# Digital_-_STM32.net
KiCad netlist of a schematic drawn in Altium Designer
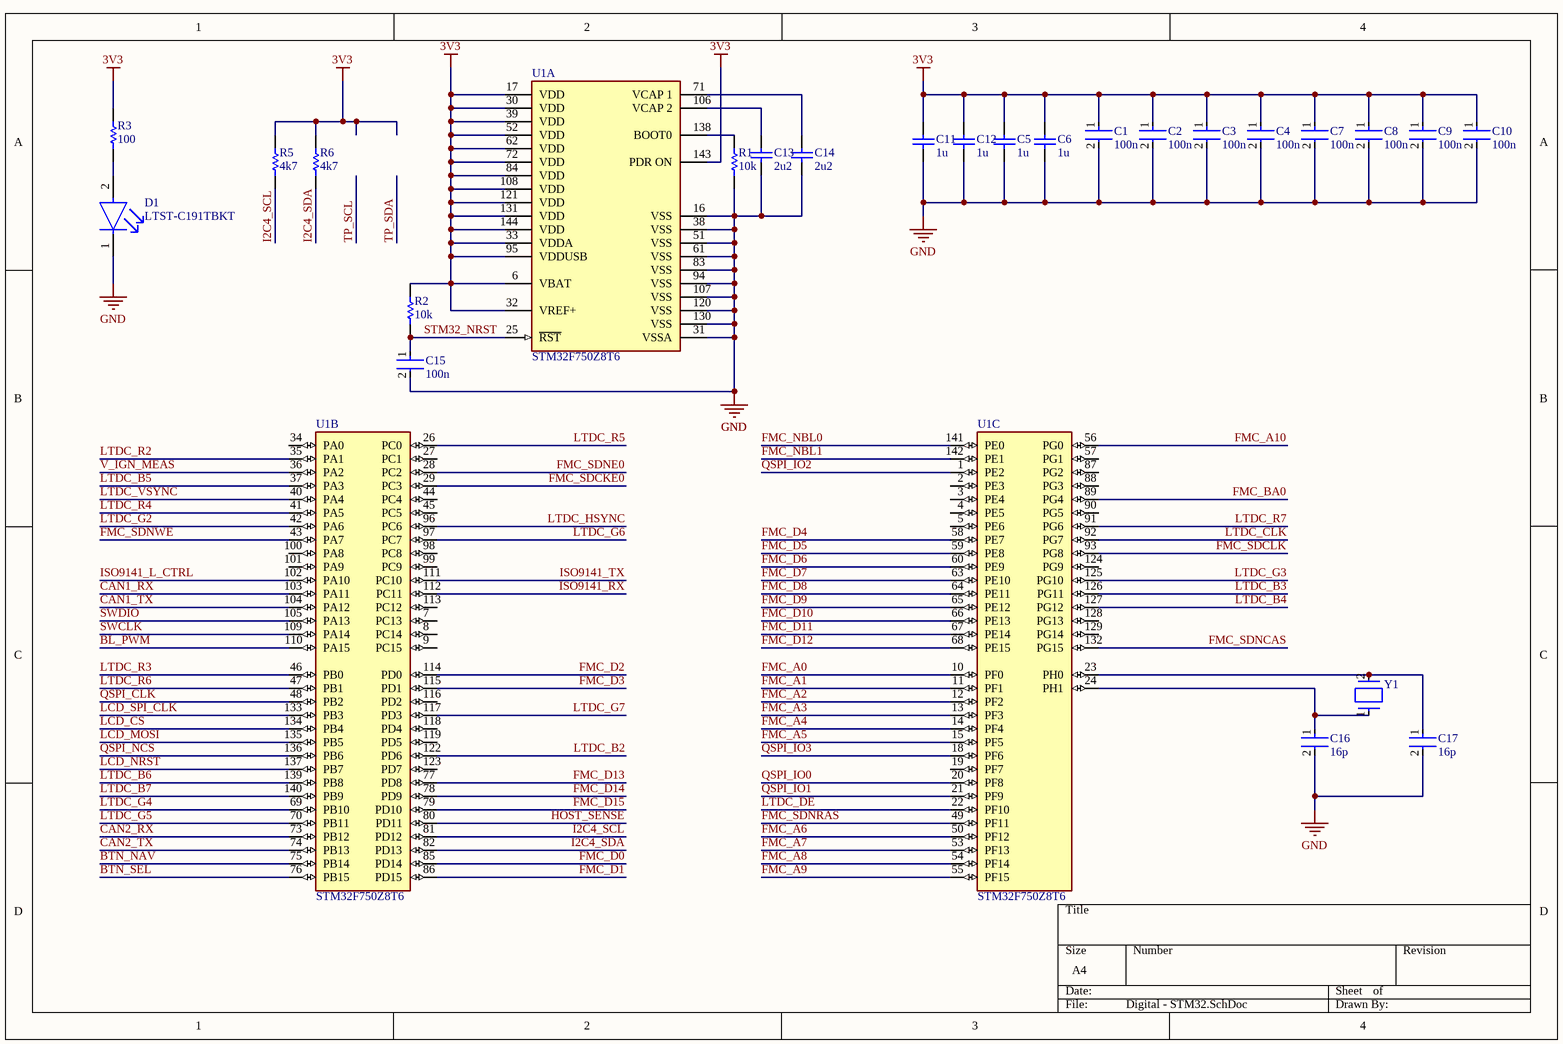
[diagram p0: Digital - STM32.SchDoc]

(export (version "E")
  (design (tool "Eeschema 10.0.6"))
  (components
    (comp (ref "C1")
      (value "100n")
      (footprint "FP-GRM188-0_1-e0_2_0_55-IPC_A")
      (description "Chip Multilayer Ceramic Capacitors for General Purpose, 0603, 10uF, X5R, 15%, 20%, 6.3V")
      (fields (field (name "VOLTAGE") "6.3V") (field (name "TOLERANCE") "20%"))
      (libsource (lib "Altium Content Vault") (part "02cd4be3c70576c341d710602a673aa"))
    )
    (comp (ref "C2")
      (value "100n")
      (footprint "FP-GRM188-0_1-e0_2_0_55-IPC_A")
      (description "Chip Multilayer Ceramic Capacitors for General Purpose, 0603, 10uF, X5R, 15%, 20%, 6.3V")
      (fields (field (name "VOLTAGE") "6.3V") (field (name "TOLERANCE") "20%"))
      (libsource (lib "Altium Content Vault") (part "02cd4be3c70576c341d710602a673aa"))
    )
    (comp (ref "C3")
      (value "100n")
      (footprint "FP-GRM188-0_1-e0_2_0_55-IPC_A")
      (description "Chip Multilayer Ceramic Capacitors for General Purpose, 0603, 10uF, X5R, 15%, 20%, 6.3V")
      (fields (field (name "VOLTAGE") "6.3V") (field (name "TOLERANCE") "20%"))
      (libsource (lib "Altium Content Vault") (part "02cd4be3c70576c341d710602a673aa"))
    )
    (comp (ref "C4")
      (value "100n")
      (footprint "FP-GRM188-0_1-e0_2_0_55-IPC_A")
      (description "Chip Multilayer Ceramic Capacitors for General Purpose, 0603, 10uF, X5R, 15%, 20%, 6.3V")
      (fields (field (name "VOLTAGE") "6.3V") (field (name "TOLERANCE") "20%"))
      (libsource (lib "Altium Content Vault") (part "02cd4be3c70576c341d710602a673aa"))
    )
    (comp (ref "C5")
      (value "1u")
      (footprint "CAPC2013X135X45LL10T25")
      (description "Chip Capacitor, 4.7 uF, +/- 10%, 16 V, -55 to 85 degC, 0805 (2012 Metric), RoHS, Tape and Reel")
      (fields (field (name "TOLERANCE") "10%") (field (name "PARTNUMBER") "GRM21BR61C475KA88L"))
      (libsource (lib "Altium Content Vault") (part "CAP-NP-2"))
    )
    (comp (ref "C6")
      (value "1u")
      (footprint "CAPC2013X135X45LL10T25")
      (description "Chip Capacitor, 4.7 uF, +/- 10%, 16 V, -55 to 85 degC, 0805 (2012 Metric), RoHS, Tape and Reel")
      (fields (field (name "TOLERANCE") "10%") (field (name "PARTNUMBER") "GRM21BR61C475KA88L"))
      (libsource (lib "Altium Content Vault") (part "CAP-NP-2"))
    )
    (comp (ref "C7")
      (value "100n")
      (footprint "FP-GRM188-0_1-e0_2_0_55-IPC_A")
      (description "Chip Multilayer Ceramic Capacitors for General Purpose, 0603, 10uF, X5R, 15%, 20%, 6.3V")
      (fields (field (name "VOLTAGE") "6.3V") (field (name "TOLERANCE") "20%"))
      (libsource (lib "Altium Content Vault") (part "02cd4be3c70576c341d710602a673aa"))
    )
    (comp (ref "C8")
      (value "100n")
      (footprint "FP-GRM188-0_1-e0_2_0_55-IPC_A")
      (description "Chip Multilayer Ceramic Capacitors for General Purpose, 0603, 10uF, X5R, 15%, 20%, 6.3V")
      (fields (field (name "VOLTAGE") "6.3V") (field (name "TOLERANCE") "20%"))
      (libsource (lib "Altium Content Vault") (part "02cd4be3c70576c341d710602a673aa"))
    )
    (comp (ref "C9")
      (value "100n")
      (footprint "FP-GRM188-0_1-e0_2_0_55-IPC_A")
      (description "Chip Multilayer Ceramic Capacitors for General Purpose, 0603, 10uF, X5R, 15%, 20%, 6.3V")
      (fields (field (name "VOLTAGE") "6.3V") (field (name "TOLERANCE") "20%"))
      (libsource (lib "Altium Content Vault") (part "02cd4be3c70576c341d710602a673aa"))
    )
    (comp (ref "C10")
      (value "100n")
      (footprint "FP-GRM188-0_1-e0_2_0_55-IPC_A")
      (description "Chip Multilayer Ceramic Capacitors for General Purpose, 0603, 10uF, X5R, 15%, 20%, 6.3V")
      (fields (field (name "VOLTAGE") "6.3V") (field (name "TOLERANCE") "20%"))
      (libsource (lib "Altium Content Vault") (part "02cd4be3c70576c341d710602a673aa"))
    )
    (comp (ref "C11")
      (value "1u")
      (footprint "CAPC2013X135X45LL10T25")
      (description "Chip Capacitor, 4.7 uF, +/- 10%, 16 V, -55 to 85 degC, 0805 (2012 Metric), RoHS, Tape and Reel")
      (fields (field (name "TOLERANCE") "10%") (field (name "PARTNUMBER") "GRM21BR61C475KA88L"))
      (libsource (lib "Altium Content Vault") (part "CAP-NP-2"))
    )
    (comp (ref "C12")
      (value "1u")
      (footprint "CAPC2013X135X45LL10T25")
      (description "Chip Capacitor, 4.7 uF, +/- 10%, 16 V, -55 to 85 degC, 0805 (2012 Metric), RoHS, Tape and Reel")
      (fields (field (name "TOLERANCE") "10%") (field (name "PARTNUMBER") "GRM21BR61C475KA88L"))
      (libsource (lib "Altium Content Vault") (part "CAP-NP-2"))
    )
    (comp (ref "C13")
      (value "2u2")
      (footprint "CAPC2013X135X45LL10T25")
      (description "Chip Capacitor, 4.7 uF, +/- 10%, 16 V, -55 to 85 degC, 0805 (2012 Metric), RoHS, Tape and Reel")
      (fields (field (name "TOLERANCE") "10%") (field (name "PARTNUMBER") "GRM21BR61C475KA88L"))
      (libsource (lib "Altium Content Vault") (part "CAP-NP-2"))
    )
    (comp (ref "C14")
      (value "2u2")
      (footprint "CAPC2013X135X45LL10T25")
      (description "Chip Capacitor, 4.7 uF, +/- 10%, 16 V, -55 to 85 degC, 0805 (2012 Metric), RoHS, Tape and Reel")
      (fields (field (name "TOLERANCE") "10%") (field (name "PARTNUMBER") "GRM21BR61C475KA88L"))
      (libsource (lib "Altium Content Vault") (part "CAP-NP-2"))
    )
    (comp (ref "C15")
      (value "100n")
      (footprint "FP-GRM188-0_1-e0_2_0_55-IPC_A")
      (description "Chip Multilayer Ceramic Capacitors for General Purpose, 0603, 10uF, X5R, 15%, 20%, 6.3V")
      (fields (field (name "VOLTAGE") "6.3V") (field (name "TOLERANCE") "20%"))
      (libsource (lib "Altium Content Vault") (part "02cd4be3c70576c341d710602a673aa"))
    )
    (comp (ref "C16")
      (value "16p")
      (footprint "FP-GRM188-0_1-e0_2_0_55-IPC_A")
      (description "Chip Multilayer Ceramic Capacitors for General Purpose, 0603, 10uF, X5R, 15%, 20%, 6.3V")
      (fields (field (name "VOLTAGE") "6.3V") (field (name "TOLERANCE") "20%"))
      (libsource (lib "Altium Content Vault") (part "02cd4be3c70576c341d710602a673aa"))
    )
    (comp (ref "C17")
      (value "16p")
      (footprint "FP-GRM188-0_1-e0_2_0_55-IPC_A")
      (description "Chip Multilayer Ceramic Capacitors for General Purpose, 0603, 10uF, X5R, 15%, 20%, 6.3V")
      (fields (field (name "VOLTAGE") "6.3V") (field (name "TOLERANCE") "20%"))
      (libsource (lib "Altium Content Vault") (part "02cd4be3c70576c341d710602a673aa"))
    )
    (comp (ref "D1")
      (value "LTST-C191TBKT")
      (footprint "FP-LTST-C191TBKT-MFG")
      (description "LED BLUE CLEAR CHIP SMD")
      (libsource (lib "Altium Content Vault") (part "8706943c75ba83719d021d2fdc84c58"))
    )
    (comp (ref "R1")
      (value "10k")
      (footprint "RESC1608X55X30ML15T15")
      (fields (field (name "PART NUMBER") "ERJ-3EKF1003V") (field (name "MANUFACTURER") "Panasonic"))
      (libsource (lib "Altium Content Vault") (part "RES"))
    )
    (comp (ref "R2")
      (value "10k")
      (footprint "RESC1608X55X30ML15T15")
      (fields (field (name "PART NUMBER") "ERJ-3EKF1003V") (field (name "MANUFACTURER") "Panasonic"))
      (libsource (lib "Altium Content Vault") (part "RES"))
    )
    (comp (ref "R3")
      (value "100")
      (footprint "RESC1608X55X30ML15T15")
      (fields (field (name "PART NUMBER") "ERJ-3EKF1003V") (field (name "MANUFACTURER") "Panasonic"))
      (libsource (lib "Altium Content Vault") (part "RES"))
    )
    (comp (ref "R5")
      (value "4k7")
      (footprint "RESC1608X55X30ML15T15")
      (fields (field (name "PART NUMBER") "ERJ-3EKF1003V") (field (name "MANUFACTURER") "Panasonic"))
      (libsource (lib "Altium Content Vault") (part "RES"))
    )
    (comp (ref "R6")
      (value "4k7")
      (footprint "RESC1608X55X30ML15T15")
      (fields (field (name "PART NUMBER") "ERJ-3EKF1003V") (field (name "MANUFACTURER") "Panasonic"))
      (libsource (lib "Altium Content Vault") (part "RES"))
    )
    (comp (ref "U1")
      (value "STM32F750Z8T6")
      (footprint "FP-LQFP144-1A-MFG")
      (description "IC MCU 32BIT 64KB FLASH 144LQFP")
      (fields
        (field (name "MANUFACTURER") "STMicroelectronics")
        (field (name "OCTOPART") "https://octopart.com/stm32f750z8t6-stmicroelectronics-94048545")
      )
      (libsource (lib "Altium Content Vault") (part "1b3660c51b2871d5e5de1e944f1bdf6"))
    )
    (comp (ref "Y1")
      (value "ABM7-16.000MHZ-D2Y-T")
      (footprint "FP-ABM7-MFG")
      (description "Crystal 16MHz ±20ppm 18pF SMD-2 6mm x 3.5mm")
      (fields (field (name "TOLERANCE") "20ppm"))
      (libsource (lib "Altium Content Vault") (part "c23a69dc6c9e2f18f2079038eb95dd1"))
    )
  )
  (nets
    (net (code "1") (name "/BL_PWM") (class "Default")
      (node (ref "U1") (pin "110") (pinfunction "PA15_110") (pintype "bidirectional"))
    )
    (net (code "2") (name "/BTN_NAV") (class "Default")
      (node (ref "U1") (pin "75") (pinfunction "PB14_75") (pintype "bidirectional"))
    )
    (net (code "3") (name "/BTN_SEL") (class "Default")
      (node (ref "U1") (pin "76") (pinfunction "PB15_76") (pintype "bidirectional"))
    )
    (net (code "4") (name "/CAN1_RX") (class "Default")
      (node (ref "U1") (pin "103") (pinfunction "PA11_103") (pintype "bidirectional"))
    )
    (net (code "5") (name "/CAN1_TX") (class "Default")
      (node (ref "U1") (pin "104") (pinfunction "PA12_104") (pintype "bidirectional"))
    )
    (net (code "6") (name "/CAN2_RX") (class "Default")
      (node (ref "U1") (pin "73") (pinfunction "PB12_73") (pintype "bidirectional"))
    )
    (net (code "7") (name "/CAN2_TX") (class "Default")
      (node (ref "U1") (pin "74") (pinfunction "PB13_74") (pintype "bidirectional"))
    )
    (net (code "8") (name "/FMC_A0") (class "Default")
      (node (ref "U1") (pin "10") (pinfunction "PF0_10") (pintype "bidirectional"))
    )
    (net (code "9") (name "/FMC_A1") (class "Default")
      (node (ref "U1") (pin "11") (pinfunction "PF1_11") (pintype "bidirectional"))
    )
    (net (code "10") (name "/FMC_A2") (class "Default")
      (node (ref "U1") (pin "12") (pinfunction "PF2_12") (pintype "bidirectional"))
    )
    (net (code "11") (name "/FMC_A3") (class "Default")
      (node (ref "U1") (pin "13") (pinfunction "PF3_13") (pintype "bidirectional"))
    )
    (net (code "12") (name "/FMC_A4") (class "Default")
      (node (ref "U1") (pin "14") (pinfunction "PF4_14") (pintype "bidirectional"))
    )
    (net (code "13") (name "/FMC_A5") (class "Default")
      (node (ref "U1") (pin "15") (pinfunction "PF5_15") (pintype "bidirectional"))
    )
    (net (code "14") (name "/FMC_A6") (class "Default")
      (node (ref "U1") (pin "50") (pinfunction "PF12_50") (pintype "bidirectional"))
    )
    (net (code "15") (name "/FMC_A7") (class "Default")
      (node (ref "U1") (pin "53") (pinfunction "PF13_53") (pintype "bidirectional"))
    )
    (net (code "16") (name "/FMC_A8") (class "Default")
      (node (ref "U1") (pin "54") (pinfunction "PF14_54") (pintype "bidirectional"))
    )
    (net (code "17") (name "/FMC_A9") (class "Default")
      (node (ref "U1") (pin "55") (pinfunction "PF15_55") (pintype "bidirectional"))
    )
    (net (code "18") (name "/FMC_A10") (class "Default")
      (node (ref "U1") (pin "56") (pinfunction "PG0_56") (pintype "bidirectional"))
    )
    (net (code "19") (name "/FMC_BA0") (class "Default")
      (node (ref "U1") (pin "89") (pinfunction "PG4_89") (pintype "bidirectional"))
    )
    (net (code "20") (name "/FMC_D0") (class "Default")
      (node (ref "U1") (pin "85") (pinfunction "PD14_85") (pintype "bidirectional"))
    )
    (net (code "21") (name "/FMC_D1") (class "Default")
      (node (ref "U1") (pin "86") (pinfunction "PD15_86") (pintype "bidirectional"))
    )
    (net (code "22") (name "/FMC_D2") (class "Default")
      (node (ref "U1") (pin "114") (pinfunction "PD0_114") (pintype "bidirectional"))
    )
    (net (code "23") (name "/FMC_D3") (class "Default")
      (node (ref "U1") (pin "115") (pinfunction "PD1_115") (pintype "bidirectional"))
    )
    (net (code "24") (name "/FMC_D4") (class "Default")
      (node (ref "U1") (pin "58") (pinfunction "PE7_58") (pintype "bidirectional"))
    )
    (net (code "25") (name "/FMC_D5") (class "Default")
      (node (ref "U1") (pin "59") (pinfunction "PE8_59") (pintype "bidirectional"))
    )
    (net (code "26") (name "/FMC_D6") (class "Default")
      (node (ref "U1") (pin "60") (pinfunction "PE9_60") (pintype "bidirectional"))
    )
    (net (code "27") (name "/FMC_D7") (class "Default")
      (node (ref "U1") (pin "63") (pinfunction "PE10_63") (pintype "bidirectional"))
    )
    (net (code "28") (name "/FMC_D8") (class "Default")
      (node (ref "U1") (pin "64") (pinfunction "PE11_64") (pintype "bidirectional"))
    )
    (net (code "29") (name "/FMC_D9") (class "Default")
      (node (ref "U1") (pin "65") (pinfunction "PE12_65") (pintype "bidirectional"))
    )
    (net (code "30") (name "/FMC_D10") (class "Default")
      (node (ref "U1") (pin "66") (pinfunction "PE13_66") (pintype "bidirectional"))
    )
    (net (code "31") (name "/FMC_D11") (class "Default")
      (node (ref "U1") (pin "67") (pinfunction "PE14_67") (pintype "bidirectional"))
    )
    (net (code "32") (name "/FMC_D12") (class "Default")
      (node (ref "U1") (pin "68") (pinfunction "PE15_68") (pintype "bidirectional"))
    )
    (net (code "33") (name "/FMC_D13") (class "Default")
      (node (ref "U1") (pin "77") (pinfunction "PD8_77") (pintype "bidirectional"))
    )
    (net (code "34") (name "/FMC_D14") (class "Default")
      (node (ref "U1") (pin "78") (pinfunction "PD9_78") (pintype "bidirectional"))
    )
    (net (code "35") (name "/FMC_D15") (class "Default")
      (node (ref "U1") (pin "79") (pinfunction "PD10_79") (pintype "bidirectional"))
    )
    (net (code "36") (name "/FMC_NBL0") (class "Default")
      (node (ref "U1") (pin "141") (pinfunction "PE0_141") (pintype "bidirectional"))
    )
    (net (code "37") (name "/FMC_NBL1") (class "Default")
      (node (ref "U1") (pin "142") (pinfunction "PE1_142") (pintype "bidirectional"))
    )
    (net (code "38") (name "/FMC_SDCKE0") (class "Default")
      (node (ref "U1") (pin "29") (pinfunction "PC3_29") (pintype "bidirectional"))
    )
    (net (code "39") (name "/FMC_SDCLK") (class "Default")
      (node (ref "U1") (pin "93") (pinfunction "PG8_93") (pintype "bidirectional"))
    )
    (net (code "40") (name "/FMC_SDNCAS") (class "Default")
      (node (ref "U1") (pin "132") (pinfunction "PG15_132") (pintype "bidirectional"))
    )
    (net (code "41") (name "/FMC_SDNE0") (class "Default")
      (node (ref "U1") (pin "28") (pinfunction "PC2_28") (pintype "bidirectional"))
    )
    (net (code "42") (name "/FMC_SDNRAS") (class "Default")
      (node (ref "U1") (pin "49") (pinfunction "PF11_49") (pintype "bidirectional"))
    )
    (net (code "43") (name "/FMC_SDNWE") (class "Default")
      (node (ref "U1") (pin "43") (pinfunction "PA7_43") (pintype "bidirectional"))
    )
    (net (code "44") (name "/HOST_SENSE") (class "Default")
      (node (ref "U1") (pin "80") (pinfunction "PD11_80") (pintype "bidirectional"))
    )
    (net (code "45") (name "/I2C4_SCL") (class "Default")
      (node (ref "R5") (pin "1") (pinfunction "1_1") (pintype "passive"))
      (node (ref "U1") (pin "81") (pinfunction "PD12_81") (pintype "bidirectional"))
    )
    (net (code "46") (name "/I2C4_SDA") (class "Default")
      (node (ref "R6") (pin "1") (pinfunction "1_1") (pintype "passive"))
      (node (ref "U1") (pin "82") (pinfunction "PD13_82") (pintype "bidirectional"))
    )
    (net (code "47") (name "/ISO9141_L_CTRL") (class "Default")
      (node (ref "U1") (pin "102") (pinfunction "PA10_102") (pintype "bidirectional"))
    )
    (net (code "48") (name "/ISO9141_RX") (class "Default")
      (node (ref "U1") (pin "112") (pinfunction "PC11_112") (pintype "bidirectional"))
    )
    (net (code "49") (name "/ISO9141_TX") (class "Default")
      (node (ref "U1") (pin "111") (pinfunction "PC10_111") (pintype "bidirectional"))
    )
    (net (code "50") (name "/LCD_CS") (class "Default")
      (node (ref "U1") (pin "134") (pinfunction "PB4_134") (pintype "bidirectional"))
    )
    (net (code "51") (name "/LCD_MOSI") (class "Default")
      (node (ref "U1") (pin "135") (pinfunction "PB5_135") (pintype "bidirectional"))
    )
    (net (code "52") (name "/LCD_NRST") (class "Default")
      (node (ref "U1") (pin "137") (pinfunction "PB7_137") (pintype "bidirectional"))
    )
    (net (code "53") (name "/LCD_SPI_CLK") (class "Default")
      (node (ref "U1") (pin "133") (pinfunction "PB3_133") (pintype "bidirectional"))
    )
    (net (code "54") (name "/LTDC_B2") (class "Default")
      (node (ref "U1") (pin "122") (pinfunction "PD6_122") (pintype "bidirectional"))
    )
    (net (code "55") (name "/LTDC_B3") (class "Default")
      (node (ref "U1") (pin "126") (pinfunction "PG11_126") (pintype "bidirectional"))
    )
    (net (code "56") (name "/LTDC_B4") (class "Default")
      (node (ref "U1") (pin "127") (pinfunction "PG12_127") (pintype "bidirectional"))
    )
    (net (code "57") (name "/LTDC_B5") (class "Default")
      (node (ref "U1") (pin "37") (pinfunction "PA3_37") (pintype "bidirectional"))
    )
    (net (code "58") (name "/LTDC_B6") (class "Default")
      (node (ref "U1") (pin "139") (pinfunction "PB8_139") (pintype "bidirectional"))
    )
    (net (code "59") (name "/LTDC_B7") (class "Default")
      (node (ref "U1") (pin "140") (pinfunction "PB9_140") (pintype "bidirectional"))
    )
    (net (code "60") (name "/LTDC_CLK") (class "Default")
      (node (ref "U1") (pin "92") (pinfunction "PG7_92") (pintype "bidirectional"))
    )
    (net (code "61") (name "/LTDC_DE") (class "Default")
      (node (ref "U1") (pin "22") (pinfunction "PF10_22") (pintype "bidirectional"))
    )
    (net (code "62") (name "/LTDC_G2") (class "Default")
      (node (ref "U1") (pin "42") (pinfunction "PA6_42") (pintype "bidirectional"))
    )
    (net (code "63") (name "/LTDC_G3") (class "Default")
      (node (ref "U1") (pin "125") (pinfunction "PG10_125") (pintype "bidirectional"))
    )
    (net (code "64") (name "/LTDC_G4") (class "Default")
      (node (ref "U1") (pin "69") (pinfunction "PB10_69") (pintype "bidirectional"))
    )
    (net (code "65") (name "/LTDC_G5") (class "Default")
      (node (ref "U1") (pin "70") (pinfunction "PB11_70") (pintype "bidirectional"))
    )
    (net (code "66") (name "/LTDC_G6") (class "Default")
      (node (ref "U1") (pin "97") (pinfunction "PC7_97") (pintype "bidirectional"))
    )
    (net (code "67") (name "/LTDC_G7") (class "Default")
      (node (ref "U1") (pin "117") (pinfunction "PD3_117") (pintype "bidirectional"))
    )
    (net (code "68") (name "/LTDC_HSYNC") (class "Default")
      (node (ref "U1") (pin "96") (pinfunction "PC6_96") (pintype "bidirectional"))
    )
    (net (code "69") (name "/LTDC_R2") (class "Default")
      (node (ref "U1") (pin "35") (pinfunction "PA1_35") (pintype "bidirectional"))
    )
    (net (code "70") (name "/LTDC_R3") (class "Default")
      (node (ref "U1") (pin "46") (pinfunction "PB0_46") (pintype "bidirectional"))
    )
    (net (code "71") (name "/LTDC_R4") (class "Default")
      (node (ref "U1") (pin "41") (pinfunction "PA5_41") (pintype "bidirectional"))
    )
    (net (code "72") (name "/LTDC_R5") (class "Default")
      (node (ref "U1") (pin "26") (pinfunction "PC0_26") (pintype "bidirectional"))
    )
    (net (code "73") (name "/LTDC_R6") (class "Default")
      (node (ref "U1") (pin "47") (pinfunction "PB1_47") (pintype "bidirectional"))
    )
    (net (code "74") (name "/LTDC_R7") (class "Default")
      (node (ref "U1") (pin "91") (pinfunction "PG6_91") (pintype "bidirectional"))
    )
    (net (code "75") (name "/LTDC_VSYNC") (class "Default")
      (node (ref "U1") (pin "40") (pinfunction "PA4_40") (pintype "bidirectional"))
    )
    (net (code "76") (name "/QSPI_CLK") (class "Default")
      (node (ref "U1") (pin "48") (pinfunction "PB2_48") (pintype "bidirectional"))
    )
    (net (code "77") (name "/QSPI_IO0") (class "Default")
      (node (ref "U1") (pin "20") (pinfunction "PF8_20") (pintype "bidirectional"))
    )
    (net (code "78") (name "/QSPI_IO1") (class "Default")
      (node (ref "U1") (pin "21") (pinfunction "PF9_21") (pintype "bidirectional"))
    )
    (net (code "79") (name "/QSPI_IO2") (class "Default")
      (node (ref "U1") (pin "1") (pinfunction "PE2_1") (pintype "bidirectional"))
    )
    (net (code "80") (name "/QSPI_IO3") (class "Default")
      (node (ref "U1") (pin "18") (pinfunction "PF6_18") (pintype "bidirectional"))
    )
    (net (code "81") (name "/QSPI_NCS") (class "Default")
      (node (ref "U1") (pin "136") (pinfunction "PB6_136") (pintype "bidirectional"))
    )
    (net (code "82") (name "/STM32_NRST") (class "Default")
      (node (ref "C15") (pin "1") (pinfunction "1_1") (pintype "passive"))
      (node (ref "R2") (pin "1") (pinfunction "1_1") (pintype "passive"))
      (node (ref "U1") (pin "25") (pinfunction "~{RST}_25") (pintype "input"))
    )
    (net (code "83") (name "/SWCLK") (class "Default")
      (node (ref "U1") (pin "109") (pinfunction "PA14_109") (pintype "bidirectional"))
    )
    (net (code "84") (name "/SWDIO") (class "Default")
      (node (ref "U1") (pin "105") (pinfunction "PA13_105") (pintype "bidirectional"))
    )
    (net (code "87") (name "/V_IGN_MEAS") (class "Default")
      (node (ref "U1") (pin "36") (pinfunction "PA2_36") (pintype "bidirectional"))
    )
    (net (code "88") (name "3V3") (class "Default")
      (node (ref "C1") (pin "1") (pinfunction "1_1") (pintype "passive"))
      (node (ref "C10") (pin "1") (pinfunction "1_1") (pintype "passive"))
      (node (ref "C11") (pin "2") (pinfunction "2_2") (pintype "passive"))
      (node (ref "C12") (pin "2") (pinfunction "2_2") (pintype "passive"))
      (node (ref "C2") (pin "1") (pinfunction "1_1") (pintype "passive"))
      (node (ref "C3") (pin "1") (pinfunction "1_1") (pintype "passive"))
      (node (ref "C4") (pin "1") (pinfunction "1_1") (pintype "passive"))
      (node (ref "C5") (pin "2") (pinfunction "2_2") (pintype "passive"))
      (node (ref "C6") (pin "2") (pinfunction "2_2") (pintype "passive"))
      (node (ref "C7") (pin "1") (pinfunction "1_1") (pintype "passive"))
      (node (ref "C8") (pin "1") (pinfunction "1_1") (pintype "passive"))
      (node (ref "C9") (pin "1") (pinfunction "1_1") (pintype "passive"))
      (node (ref "R2") (pin "2") (pinfunction "2_2") (pintype "passive"))
      (node (ref "R3") (pin "2") (pinfunction "2_2") (pintype "passive"))
      (node (ref "R5") (pin "2") (pinfunction "2_2") (pintype "passive"))
      (node (ref "R6") (pin "2") (pinfunction "2_2") (pintype "passive"))
      (node (ref "U1") (pin "108") (pinfunction "VDD_108") (pintype "power_in"))
      (node (ref "U1") (pin "121") (pinfunction "VDD_121") (pintype "power_in"))
      (node (ref "U1") (pin "131") (pinfunction "VDD_131") (pintype "power_in"))
      (node (ref "U1") (pin "143") (pinfunction "PDR_ON_143") (pintype "power_in"))
      (node (ref "U1") (pin "144") (pinfunction "VDD_144") (pintype "power_in"))
      (node (ref "U1") (pin "17") (pinfunction "VDD_17") (pintype "power_in"))
      (node (ref "U1") (pin "30") (pinfunction "VDD_30") (pintype "power_in"))
      (node (ref "U1") (pin "32") (pinfunction "VREF+_32") (pintype "power_in"))
      (node (ref "U1") (pin "33") (pinfunction "VDDA_33") (pintype "power_in"))
      (node (ref "U1") (pin "39") (pinfunction "VDD_39") (pintype "power_in"))
      (node (ref "U1") (pin "52") (pinfunction "VDD_52") (pintype "power_in"))
      (node (ref "U1") (pin "6") (pinfunction "VBAT_6") (pintype "power_in"))
      (node (ref "U1") (pin "62") (pinfunction "VDD_62") (pintype "power_in"))
      (node (ref "U1") (pin "72") (pinfunction "VDD_72") (pintype "power_in"))
      (node (ref "U1") (pin "84") (pinfunction "VDD_84") (pintype "power_in"))
      (node (ref "U1") (pin "95") (pinfunction "VDDUSB_95") (pintype "power_in"))
    )
    (net (code "89") (name "GND") (class "Default")
      (node (ref "C1") (pin "2") (pinfunction "2_2") (pintype "passive"))
      (node (ref "C10") (pin "2") (pinfunction "2_2") (pintype "passive"))
      (node (ref "C11") (pin "1") (pinfunction "1_1") (pintype "passive"))
      (node (ref "C12") (pin "1") (pinfunction "1_1") (pintype "passive"))
      (node (ref "C13") (pin "1") (pinfunction "1_1") (pintype "passive"))
      (node (ref "C14") (pin "1") (pinfunction "1_1") (pintype "passive"))
      (node (ref "C15") (pin "2") (pinfunction "2_2") (pintype "passive"))
      (node (ref "C16") (pin "2") (pinfunction "2_2") (pintype "passive"))
      (node (ref "C17") (pin "2") (pinfunction "2_2") (pintype "passive"))
      (node (ref "C2") (pin "2") (pinfunction "2_2") (pintype "passive"))
      (node (ref "C3") (pin "2") (pinfunction "2_2") (pintype "passive"))
      (node (ref "C4") (pin "2") (pinfunction "2_2") (pintype "passive"))
      (node (ref "C5") (pin "1") (pinfunction "1_1") (pintype "passive"))
      (node (ref "C6") (pin "1") (pinfunction "1_1") (pintype "passive"))
      (node (ref "C7") (pin "2") (pinfunction "2_2") (pintype "passive"))
      (node (ref "C8") (pin "2") (pinfunction "2_2") (pintype "passive"))
      (node (ref "C9") (pin "2") (pinfunction "2_2") (pintype "passive"))
      (node (ref "D1") (pin "1") (pinfunction "C_1") (pintype "passive"))
      (node (ref "R1") (pin "1") (pinfunction "1_1") (pintype "passive"))
      (node (ref "U1") (pin "107") (pinfunction "VSS_107") (pintype "power_in"))
      (node (ref "U1") (pin "120") (pinfunction "VSS_120") (pintype "power_in"))
      (node (ref "U1") (pin "130") (pinfunction "VSS_130") (pintype "power_in"))
      (node (ref "U1") (pin "16") (pinfunction "VSS_16") (pintype "power_in"))
      (node (ref "U1") (pin "31") (pinfunction "VSSA_31") (pintype "power_in"))
      (node (ref "U1") (pin "38") (pinfunction "VSS_38") (pintype "power_in"))
      (node (ref "U1") (pin "51") (pinfunction "VSS_51") (pintype "power_in"))
      (node (ref "U1") (pin "61") (pinfunction "VSS_61") (pintype "power_in"))
      (node (ref "U1") (pin "83") (pinfunction "VSS_83") (pintype "power_in"))
      (node (ref "U1") (pin "94") (pinfunction "VSS_94") (pintype "power_in"))
    )
    (net (code "90") (name "Net-(D1-A)") (class "Default")
      (node (ref "D1") (pin "2") (pinfunction "A_2") (pintype "passive"))
      (node (ref "R3") (pin "1") (pinfunction "1_1") (pintype "passive"))
    )
    (net (code "91") (name "Net-(U1A-BOOT0)") (class "Default")
      (node (ref "R1") (pin "2") (pinfunction "2_2") (pintype "passive"))
      (node (ref "U1") (pin "138") (pinfunction "BOOT0_138") (pintype "passive"))
    )
    (net (code "92") (name "Net-(U1A-VCAP_1)") (class "Default")
      (node (ref "C14") (pin "2") (pinfunction "2_2") (pintype "passive"))
      (node (ref "U1") (pin "71") (pinfunction "VCAP_1_71") (pintype "power_in"))
    )
    (net (code "93") (name "Net-(U1A-VCAP_2)") (class "Default")
      (node (ref "C13") (pin "2") (pinfunction "2_2") (pintype "passive"))
      (node (ref "U1") (pin "106") (pinfunction "VCAP_2_106") (pintype "power_in"))
    )
    (net (code "94") (name "Net-(U1C-PH0)") (class "Default")
      (node (ref "C17") (pin "1") (pinfunction "1_1") (pintype "passive"))
      (node (ref "U1") (pin "23") (pinfunction "PH0_23") (pintype "bidirectional"))
      (node (ref "Y1") (pin "2") (pinfunction "2_2") (pintype "passive"))
    )
    (net (code "95") (name "Net-(U1C-PH1)") (class "Default")
      (node (ref "C16") (pin "1") (pinfunction "1_1") (pintype "passive"))
      (node (ref "U1") (pin "24") (pinfunction "PH1_24") (pintype "bidirectional"))
      (node (ref "Y1") (pin "1") (pinfunction "1_1") (pintype "passive"))
    )
    (net (code "96") (name "unconnected-(U1B-PA0-Pad34)") (class "Default")
      (node (ref "U1") (pin "34") (pinfunction "PA0_34") (pintype "bidirectional"))
    )
    (net (code "97") (name "unconnected-(U1B-PA8-Pad100)") (class "Default")
      (node (ref "U1") (pin "100") (pinfunction "PA8_100") (pintype "bidirectional"))
    )
    (net (code "98") (name "unconnected-(U1B-PA9-Pad101)") (class "Default")
      (node (ref "U1") (pin "101") (pinfunction "PA9_101") (pintype "bidirectional"))
    )
    (net (code "99") (name "unconnected-(U1B-PC1-Pad27)") (class "Default")
      (node (ref "U1") (pin "27") (pinfunction "PC1_27") (pintype "bidirectional"))
    )
    (net (code "100") (name "unconnected-(U1B-PC4-Pad44)") (class "Default")
      (node (ref "U1") (pin "44") (pinfunction "PC4_44") (pintype "bidirectional"))
    )
    (net (code "101") (name "unconnected-(U1B-PC5-Pad45)") (class "Default")
      (node (ref "U1") (pin "45") (pinfunction "PC5_45") (pintype "bidirectional"))
    )
    (net (code "102") (name "unconnected-(U1B-PC8-Pad98)") (class "Default")
      (node (ref "U1") (pin "98") (pinfunction "PC8_98") (pintype "bidirectional"))
    )
    (net (code "103") (name "unconnected-(U1B-PC9-Pad99)") (class "Default")
      (node (ref "U1") (pin "99") (pinfunction "PC9_99") (pintype "bidirectional"))
    )
    (net (code "104") (name "unconnected-(U1B-PC12-Pad113)") (class "Default")
      (node (ref "U1") (pin "113") (pinfunction "PC12_113") (pintype "bidirectional"))
    )
    (net (code "105") (name "unconnected-(U1B-PC13-Pad7)") (class "Default")
      (node (ref "U1") (pin "7") (pinfunction "PC13_7") (pintype "bidirectional"))
    )
    (net (code "106") (name "unconnected-(U1B-PC14-Pad8)") (class "Default")
      (node (ref "U1") (pin "8") (pinfunction "PC14_8") (pintype "bidirectional"))
    )
    (net (code "107") (name "unconnected-(U1B-PC15-Pad9)") (class "Default")
      (node (ref "U1") (pin "9") (pinfunction "PC15_9") (pintype "bidirectional"))
    )
    (net (code "108") (name "unconnected-(U1B-PD2-Pad116)") (class "Default")
      (node (ref "U1") (pin "116") (pinfunction "PD2_116") (pintype "bidirectional"))
    )
    (net (code "109") (name "unconnected-(U1B-PD4-Pad118)") (class "Default")
      (node (ref "U1") (pin "118") (pinfunction "PD4_118") (pintype "bidirectional"))
    )
    (net (code "110") (name "unconnected-(U1B-PD5-Pad119)") (class "Default")
      (node (ref "U1") (pin "119") (pinfunction "PD5_119") (pintype "bidirectional"))
    )
    (net (code "111") (name "unconnected-(U1B-PD7-Pad123)") (class "Default")
      (node (ref "U1") (pin "123") (pinfunction "PD7_123") (pintype "bidirectional"))
    )
    (net (code "112") (name "unconnected-(U1C-PE3-Pad2)") (class "Default")
      (node (ref "U1") (pin "2") (pinfunction "PE3_2") (pintype "bidirectional"))
    )
    (net (code "113") (name "unconnected-(U1C-PE4-Pad3)") (class "Default")
      (node (ref "U1") (pin "3") (pinfunction "PE4_3") (pintype "bidirectional"))
    )
    (net (code "114") (name "unconnected-(U1C-PE5-Pad4)") (class "Default")
      (node (ref "U1") (pin "4") (pinfunction "PE5_4") (pintype "bidirectional"))
    )
    (net (code "115") (name "unconnected-(U1C-PE6-Pad5)") (class "Default")
      (node (ref "U1") (pin "5") (pinfunction "PE6_5") (pintype "bidirectional"))
    )
    (net (code "116") (name "unconnected-(U1C-PF7-Pad19)") (class "Default")
      (node (ref "U1") (pin "19") (pinfunction "PF7_19") (pintype "bidirectional"))
    )
    (net (code "117") (name "unconnected-(U1C-PG1-Pad57)") (class "Default")
      (node (ref "U1") (pin "57") (pinfunction "PG1_57") (pintype "bidirectional"))
    )
    (net (code "118") (name "unconnected-(U1C-PG2-Pad87)") (class "Default")
      (node (ref "U1") (pin "87") (pinfunction "PG2_87") (pintype "bidirectional"))
    )
    (net (code "119") (name "unconnected-(U1C-PG3-Pad88)") (class "Default")
      (node (ref "U1") (pin "88") (pinfunction "PG3_88") (pintype "bidirectional"))
    )
    (net (code "120") (name "unconnected-(U1C-PG5-Pad90)") (class "Default")
      (node (ref "U1") (pin "90") (pinfunction "PG5_90") (pintype "bidirectional"))
    )
    (net (code "121") (name "unconnected-(U1C-PG9-Pad124)") (class "Default")
      (node (ref "U1") (pin "124") (pinfunction "PG9_124") (pintype "bidirectional"))
    )
    (net (code "122") (name "unconnected-(U1C-PG13-Pad128)") (class "Default")
      (node (ref "U1") (pin "128") (pinfunction "PG13_128") (pintype "bidirectional"))
    )
    (net (code "123") (name "unconnected-(U1C-PG14-Pad129)") (class "Default")
      (node (ref "U1") (pin "129") (pinfunction "PG14_129") (pintype "bidirectional"))
    )
  )
)
